# schematic.net
KiCad netlist of a schematic drawn in EAGLE
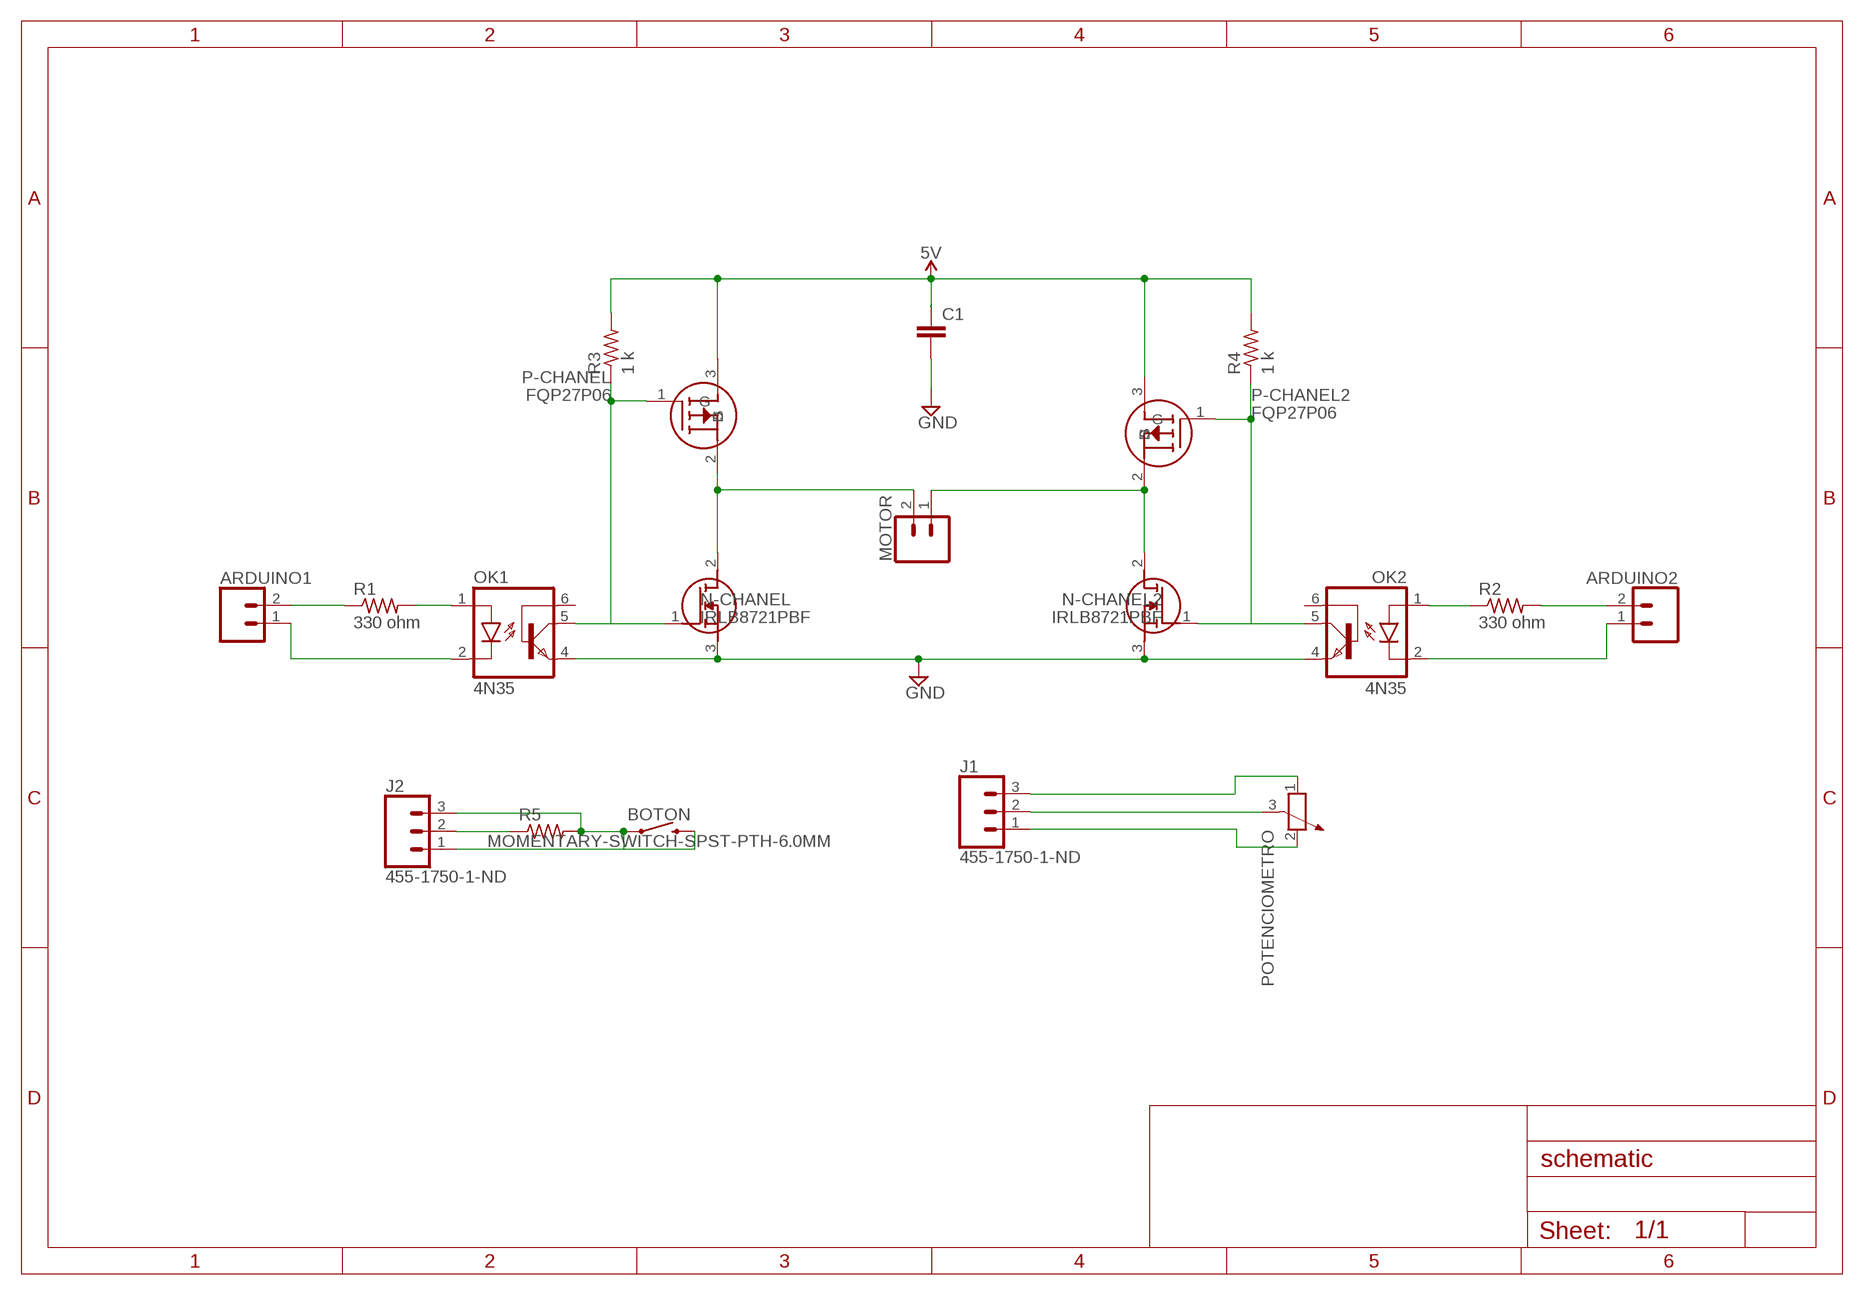
[diagram p0: schematic, sheet 1]

(export (version "E")
  (design (tool "Eeschema 10.0.6"))
  (components
    (comp (ref "ARDUINO1")
      (value "CONN_02")
      (footprint "eagle-import:1X02")
      (libsource (lib "eagle-import") (part "CONN_02"))
    )
    (comp (ref "ARDUINO2")
      (value "CONN_02")
      (footprint "eagle-import:1X02")
      (libsource (lib "eagle-import") (part "CONN_02"))
    )
    (comp (ref "BOTON")
      (value "MOMENTARY-SWITCH-SPST-PTH-6.0MM")
      (footprint "eagle-import:TACTILE_SWITCH_PTH_6.0MM")
      (libsource (lib "eagle-import") (part "MOMENTARY-SWITCH-SPST-PTH-6.0MM"))
    )
    (comp (ref "C1")
      (value "C-EUC0805")
      (footprint "eagle-import:C0805")
      (libsource (lib "eagle-import") (part "C-EUC0805"))
    )
    (comp (ref "J1")
      (value "455-1750-1-ND")
      (footprint "eagle-import:1X03")
      (libsource (lib "eagle-import") (part "CONN_03"))
    )
    (comp (ref "J2")
      (value "455-1750-1-ND")
      (footprint "eagle-import:1X03")
      (libsource (lib "eagle-import") (part "CONN_03"))
    )
    (comp (ref "MOTOR")
      (value "CONN_02")
      (footprint "eagle-import:1X02")
      (libsource (lib "eagle-import") (part "CONN_02"))
    )
    (comp (ref "N-CHANEL")
      (value "IRLB8721PBF")
      (footprint "eagle-import:TO254P483X1016X1994-3P")
      (fields
        (field (name "MOUSER_PART_NUMBER") "942-IRLB8721PBF")
        (field (name "RS_PART_NUMBER") "7259322P")
      )
      (libsource (lib "eagle-import") (part "IRLB8721PBF"))
    )
    (comp (ref "N-CHANEL2")
      (value "IRLB8721PBF")
      (footprint "eagle-import:TO254P483X1016X1994-3P")
      (fields
        (field (name "MOUSER_PART_NUMBER") "942-IRLB8721PBF")
        (field (name "RS_PART_NUMBER") "7259322P")
      )
      (libsource (lib "eagle-import") (part "IRLB8721PBF"))
    )
    (comp (ref "OK1")
      (value "4N35")
      (footprint "eagle-import:DIL06")
      (fields (field (name "MF") "FAIRCHILD SEMICONDUCTOR"))
      (libsource (lib "eagle-import") (part "4N35"))
    )
    (comp (ref "OK2")
      (value "4N35")
      (footprint "eagle-import:DIL06")
      (fields (field (name "MF") "FAIRCHILD SEMICONDUCTOR"))
      (libsource (lib "eagle-import") (part "4N35"))
    )
    (comp (ref "P-CHANEL")
      (value "FQP27P06")
      (footprint "eagle-import:TO220")
      (libsource (lib "eagle-import") (part "FQP27P06"))
    )
    (comp (ref "P-CHANEL2")
      (value "FQP27P06")
      (footprint "eagle-import:TO220")
      (libsource (lib "eagle-import") (part "FQP27P06"))
    )
    (comp (ref "POTENCIOMETRO")
      (value "POTENTIOMETER_PT-10S")
      (footprint "eagle-import:PT-10S")
      (libsource (lib "eagle-import") (part "POTENTIOMETER_PT-10S"))
    )
    (comp (ref "R1")
      (value "330 ohm")
      (footprint "eagle-import:0411_12")
      (libsource (lib "eagle-import") (part "R-US_0411/12"))
    )
    (comp (ref "R2")
      (value "330 ohm")
      (footprint "eagle-import:0411_12")
      (libsource (lib "eagle-import") (part "R-US_0411/12"))
    )
    (comp (ref "R3")
      (value "1 k")
      (footprint "eagle-import:0411_12")
      (libsource (lib "eagle-import") (part "R-US_0411/12"))
    )
    (comp (ref "R4")
      (value "1 k")
      (footprint "eagle-import:0411_12")
      (libsource (lib "eagle-import") (part "R-US_0411/12"))
    )
    (comp (ref "R5")
      (value "R-US_0411/12")
      (footprint "eagle-import:0411_12")
      (libsource (lib "eagle-import") (part "R-US_0411/12"))
    )
  )
  (nets
    (net (code "1") (name "5V") (class "Default")
      (node (ref "C1") (pin "1") (pinfunction "1_1") (pintype "passive"))
      (node (ref "P-CHANEL") (pin "3") (pinfunction "S_3") (pintype "bidirectional"))
      (node (ref "P-CHANEL2") (pin "3") (pinfunction "S_3") (pintype "bidirectional"))
      (node (ref "R3") (pin "2") (pinfunction "2_2") (pintype "passive"))
      (node (ref "R4") (pin "2") (pinfunction "2_2") (pintype "passive"))
    )
    (net (code "2") (name "GND") (class "Default")
      (node (ref "C1") (pin "2") (pinfunction "2_2") (pintype "passive"))
      (node (ref "N-CHANEL") (pin "3") (pinfunction "S_3") (pintype "bidirectional"))
      (node (ref "N-CHANEL2") (pin "3") (pinfunction "S_3") (pintype "bidirectional"))
      (node (ref "OK1") (pin "4") (pinfunction "EMI_4") (pintype "passive"))
      (node (ref "OK2") (pin "4") (pinfunction "EMI_4") (pintype "passive"))
    )
    (net (code "3") (name "Net-(ARDUINO1-Pad2)") (class "Default")
      (node (ref "ARDUINO1") (pin "2") (pinfunction "2_2") (pintype "passive"))
      (node (ref "R1") (pin "1") (pinfunction "1_1") (pintype "passive"))
    )
    (net (code "4") (name "Net-(ARDUINO2-Pad2)") (class "Default")
      (node (ref "ARDUINO2") (pin "2") (pinfunction "2_2") (pintype "passive"))
      (node (ref "R2") (pin "2") (pinfunction "2_2") (pintype "passive"))
    )
    (net (code "5") (name "Net-(BOTON-2)") (class "Default")
      (node (ref "BOTON") (pin "3") (pinfunction "2_3") (pintype "passive"))
      (node (ref "J2") (pin "1") (pinfunction "1_1") (pintype "passive"))
    )
    (net (code "6") (name "Net-(BOTON-Pad1)") (class "Default")
      (node (ref "BOTON") (pin "1") (pinfunction "1_1") (pintype "passive"))
      (node (ref "J2") (pin "3") (pinfunction "3_3") (pintype "passive"))
      (node (ref "R5") (pin "2") (pinfunction "2_2") (pintype "passive"))
    )
    (net (code "7") (name "Net-(J1-Pad1)") (class "Default")
      (node (ref "J1") (pin "1") (pinfunction "1_1") (pintype "passive"))
      (node (ref "POTENCIOMETRO") (pin "2") (pinfunction "2_2") (pintype "passive"))
    )
    (net (code "8") (name "Net-(J1-Pad2)") (class "Default")
      (node (ref "J1") (pin "2") (pinfunction "2_2") (pintype "passive"))
      (node (ref "POTENCIOMETRO") (pin "3") (pinfunction "3_3") (pintype "passive"))
    )
    (net (code "9") (name "Net-(J1-Pad3)") (class "Default")
      (node (ref "J1") (pin "3") (pinfunction "3_3") (pintype "passive"))
      (node (ref "POTENCIOMETRO") (pin "1") (pinfunction "1_1") (pintype "passive"))
    )
    (net (code "10") (name "Net-(J2-Pad2)") (class "Default")
      (node (ref "J2") (pin "2") (pinfunction "2_2") (pintype "passive"))
      (node (ref "R5") (pin "1") (pinfunction "1_1") (pintype "passive"))
    )
    (net (code "11") (name "Net-(N-CHANEL-D)") (class "Default")
      (node (ref "MOTOR") (pin "2") (pinfunction "2_2") (pintype "passive"))
      (node (ref "N-CHANEL") (pin "2") (pinfunction "D_2") (pintype "bidirectional"))
      (node (ref "P-CHANEL") (pin "2") (pinfunction "D_2") (pintype "bidirectional"))
    )
    (net (code "12") (name "Net-(N-CHANEL-G)") (class "Default")
      (node (ref "N-CHANEL") (pin "1") (pinfunction "G_1") (pintype "bidirectional"))
      (node (ref "OK1") (pin "5") (pinfunction "COL_5") (pintype "passive"))
      (node (ref "P-CHANEL") (pin "1") (pinfunction "G_1") (pintype "bidirectional"))
      (node (ref "R3") (pin "1") (pinfunction "1_1") (pintype "passive"))
    )
    (net (code "13") (name "Net-(N-CHANEL2-D)") (class "Default")
      (node (ref "MOTOR") (pin "1") (pinfunction "1_1") (pintype "passive"))
      (node (ref "N-CHANEL2") (pin "2") (pinfunction "D_2") (pintype "bidirectional"))
      (node (ref "P-CHANEL2") (pin "2") (pinfunction "D_2") (pintype "bidirectional"))
    )
    (net (code "14") (name "Net-(N-CHANEL2-G)") (class "Default")
      (node (ref "N-CHANEL2") (pin "1") (pinfunction "G_1") (pintype "bidirectional"))
      (node (ref "OK2") (pin "5") (pinfunction "COL_5") (pintype "passive"))
      (node (ref "P-CHANEL2") (pin "1") (pinfunction "G_1") (pintype "bidirectional"))
      (node (ref "R4") (pin "1") (pinfunction "1_1") (pintype "passive"))
    )
    (net (code "15") (name "Net-(OK1-A)") (class "Default")
      (node (ref "OK1") (pin "1") (pinfunction "A_1") (pintype "passive"))
      (node (ref "R1") (pin "2") (pinfunction "2_2") (pintype "passive"))
    )
    (net (code "16") (name "Net-(OK1-C)") (class "Default")
      (node (ref "ARDUINO1") (pin "1") (pinfunction "1_1") (pintype "passive"))
      (node (ref "OK1") (pin "2") (pinfunction "C_2") (pintype "passive"))
    )
    (net (code "17") (name "Net-(OK2-A)") (class "Default")
      (node (ref "OK2") (pin "1") (pinfunction "A_1") (pintype "passive"))
      (node (ref "R2") (pin "1") (pinfunction "1_1") (pintype "passive"))
    )
    (net (code "18") (name "Net-(OK2-C)") (class "Default")
      (node (ref "ARDUINO2") (pin "1") (pinfunction "1_1") (pintype "passive"))
      (node (ref "OK2") (pin "2") (pinfunction "C_2") (pintype "passive"))
    )
    (net (code "19") (name "unconnected-(OK1-BAS-Pad6)") (class "Default")
      (node (ref "OK1") (pin "6") (pinfunction "BAS_6") (pintype "passive"))
    )
    (net (code "20") (name "unconnected-(OK2-BAS-Pad6)") (class "Default")
      (node (ref "OK2") (pin "6") (pinfunction "BAS_6") (pintype "passive"))
    )
  )
)
